# Connectivity.net
KiCad netlist of a schematic drawn in Altium Designer
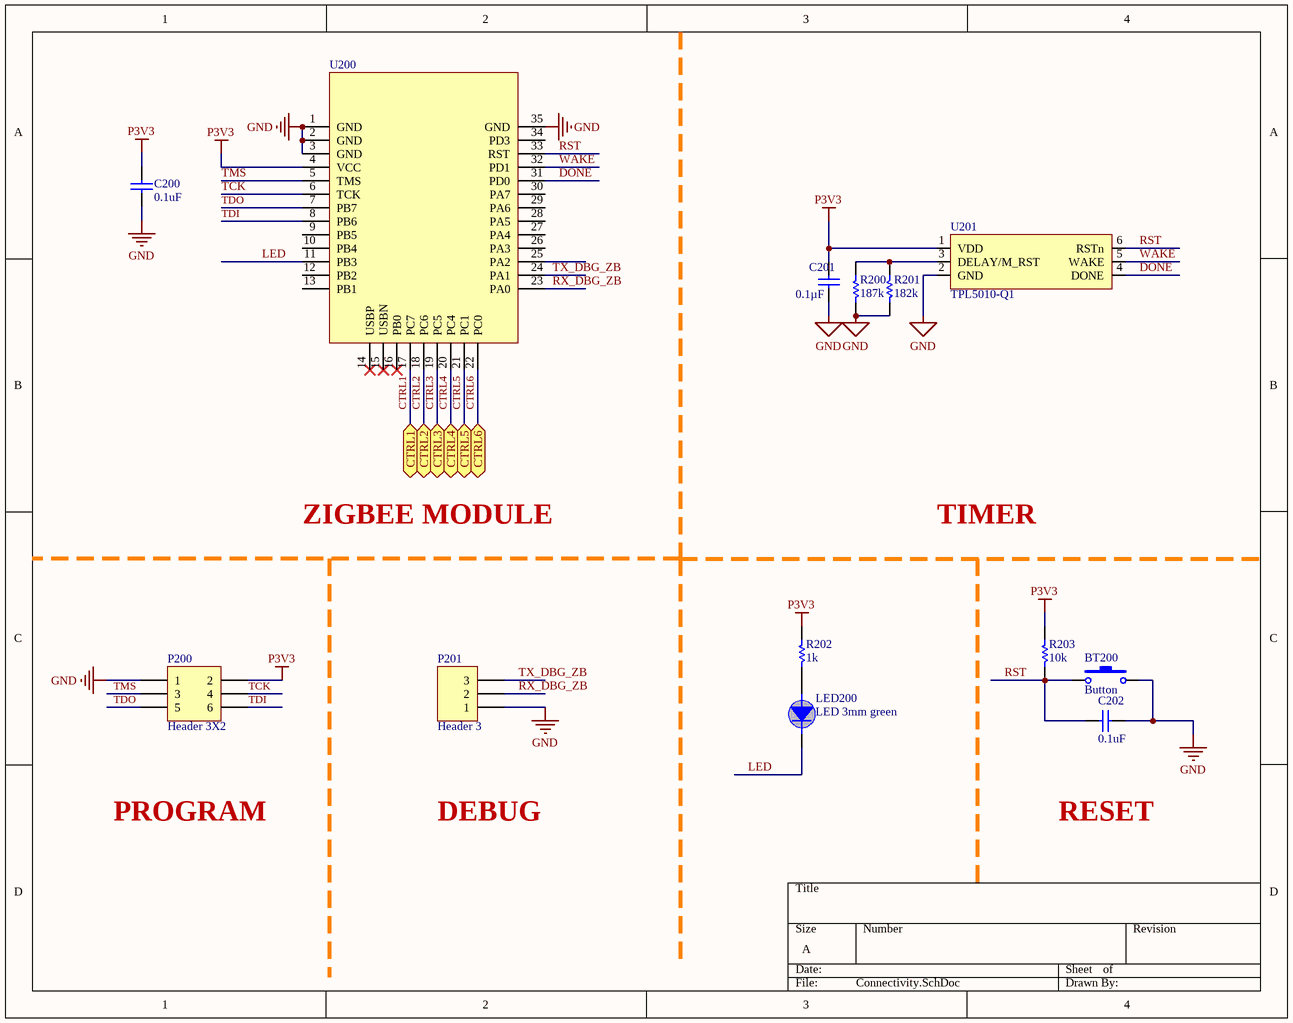
[diagram p0: Connectivity.SchDoc]

(export (version "E")
  (design (tool "Eeschema 10.0.6"))
  (components
    (comp (ref "BT200") (value "Button") (footprint "SWSMD") (libsource (lib "BinhLib") (part "Button")))
    (comp (ref "C200")
      (value "0.1uF")
      (footprint "0805 cap")
      (description "CAP CER 0.1UF 16V X7R 0402")
      (fields
        (field (name "MANUFACTURER") "Samsung Electro-Mechanics")
        (field (name "MANUFACTURER PART NUMBER") "CL05B104KO5NNNC")
      )
      (libsource (lib "BinhLib") (part "CAP0.1u0402"))
    )
    (comp (ref "C201")
      (value "0.1µF")
      (footprint "0805 cap")
      (description "CAP CER 0.1UF 10V X7R 0402")
      (fields
        (field (name "MANUFACTURER") "Taiyo Yuden")
        (field (name "MANUFACTURER PART NUMBER") "LMK105B7104KVHF")
      )
      (libsource (lib "BinhLib") (part "CAP0.1u0402"))
    )
    (comp (ref "C202") (value "0.1uF") (footprint "0805 cap") (libsource (lib "BinhLib") (part "cap SMD")))
    (comp (ref "LED200")
      (value "LED 3mm green")
      (footprint "LED 3mm green")
      (libsource (lib "BinhLib") (part "LED 3mm green"))
    )
    (comp (ref "P200")
      (value "Header 3X2")
      (footprint "HDR2X3")
      (description "Header, 3-Pin, Dual row")
      (fields (field (name "PUBLISHER") "Altium Limited"))
      (libsource (lib "BinhLib") (part "Header 3X2"))
    )
    (comp (ref "P201")
      (value "Header 3")
      (footprint "HDR1X3")
      (description "Header, 3-Pin")
      (fields (field (name "PUBLISHER") "Altium Limited"))
      (libsource (lib "BinhLib") (part "Header 3"))
    )
    (comp (ref "R200")
      (value "187k")
      (footprint "0805 Resistor")
      (description "RES SMD 187K OHM 1% 1/10W 0603")
      (fields
        (field (name "MANUFACTURER") "Panasonic Electronic Components")
        (field (name "MANUFACTURER PART NUMBER") "ERJ-3EKF1873V")
      )
      (libsource (lib "BinhLib") (part "Resistor"))
    )
    (comp (ref "R201")
      (value "182k")
      (footprint "0805 Resistor")
      (description "RES SMD 182K OHM 1% 1/10W 0603")
      (fields
        (field (name "MANUFACTURER") "Panasonic Electronic Components")
        (field (name "MANUFACTURER PART NUMBER") "ERJ-3EKF1823V")
      )
      (libsource (lib "BinhLib") (part "Resistor"))
    )
    (comp (ref "R202") (value "1k") (footprint "0805 Resistor") (libsource (lib "BinhLib") (part "Resistor")))
    (comp (ref "R203")
      (value "10k")
      (footprint "0805 Resistor")
      (libsource (lib "BinhLib") (part "Resistor"))
    )
    (comp (ref "U200")
      (value "~")
      (footprint "VZIGMOD2")
      (description "VNPT ZIGBEE MODULE V1 - No-PA")
      (fields
        (field (name "MANUFACTURER") "VNPT-Technology")
        (field (name "MANUFACTURER PART NUMBER") "VZIGMOD1")
      )
      (libsource (lib "SensorNode") (part "VZIGMOD2"))
    )
    (comp (ref "U201")
      (value "TPL5010-Q1")
      (footprint "SOT23-6")
      (description "IC TIMER W/WATCHDOG 6SOT")
      (fields
        (field (name "MANUFACTURER") "Texas Instruments")
        (field (name "MANUFACTURER PART NUMBER") "TPL5010QDDCRQ1")
      )
      (libsource (lib "BinhLib") (part "TPL5010"))
    )
  )
  (nets
    (net (code "1") (name "/CTRL1") (class "Default")
      (node (ref "U200") (pin "17") (pinfunction "PC7_17") (pintype "passive"))
    )
    (net (code "2") (name "/CTRL2") (class "Default")
      (node (ref "U200") (pin "18") (pinfunction "PC6_18") (pintype "passive"))
    )
    (net (code "3") (name "/CTRL3") (class "Default")
      (node (ref "U200") (pin "19") (pinfunction "PC5_19") (pintype "passive"))
    )
    (net (code "4") (name "/CTRL4") (class "Default")
      (node (ref "U200") (pin "20") (pinfunction "PC4_20") (pintype "passive"))
    )
    (net (code "5") (name "/CTRL5") (class "Default")
      (node (ref "U200") (pin "21") (pinfunction "PC1_21") (pintype "passive"))
    )
    (net (code "6") (name "/CTRL6") (class "Default")
      (node (ref "U200") (pin "22") (pinfunction "PC0_22") (pintype "passive"))
    )
    (net (code "7") (name "/DONE") (class "Default")
      (node (ref "U200") (pin "31") (pinfunction "PD0_31") (pintype "passive"))
      (node (ref "U201") (pin "4") (pinfunction "DONE_4") (pintype "passive"))
    )
    (net (code "8") (name "/LED") (class "Default")
      (node (ref "LED200") (pin "2") (pinfunction "Katot_2") (pintype "passive"))
      (node (ref "U200") (pin "11") (pinfunction "PB3_11") (pintype "passive"))
    )
    (net (code "9") (name "/RST") (class "Default")
      (node (ref "BT200") (pin "1") (pinfunction "1_1") (pintype "passive"))
      (node (ref "C202") (pin "2") (pintype "passive"))
      (node (ref "R203") (pin "1") (pinfunction "1_1") (pintype "passive"))
      (node (ref "U200") (pin "33") (pinfunction "RST_33") (pintype "passive"))
      (node (ref "U201") (pin "6") (pinfunction "RSTn_6") (pintype "passive"))
    )
    (net (code "10") (name "/RX_DBG_ZB") (class "Default")
      (node (ref "P201") (pin "2") (pinfunction "2_2") (pintype "passive"))
      (node (ref "U200") (pin "23") (pinfunction "PA0_23") (pintype "passive"))
    )
    (net (code "11") (name "/TCK") (class "Default")
      (node (ref "P200") (pin "4") (pinfunction "4_4") (pintype "passive"))
      (node (ref "U200") (pin "6") (pinfunction "TCK_6") (pintype "passive"))
    )
    (net (code "12") (name "/TDI") (class "Default")
      (node (ref "P200") (pin "6") (pinfunction "6_6") (pintype "passive"))
      (node (ref "U200") (pin "8") (pinfunction "PB6_8") (pintype "passive"))
    )
    (net (code "13") (name "/TDO") (class "Default")
      (node (ref "P200") (pin "5") (pinfunction "5_5") (pintype "passive"))
      (node (ref "U200") (pin "7") (pinfunction "PB7_7") (pintype "passive"))
    )
    (net (code "14") (name "/TMS") (class "Default")
      (node (ref "P200") (pin "3") (pinfunction "3_3") (pintype "passive"))
      (node (ref "U200") (pin "5") (pinfunction "TMS_5") (pintype "passive"))
    )
    (net (code "15") (name "/TX_DBG_ZB") (class "Default")
      (node (ref "P201") (pin "3") (pinfunction "3_3") (pintype "passive"))
      (node (ref "U200") (pin "24") (pinfunction "PA1_24") (pintype "passive"))
    )
    (net (code "16") (name "/WAKE") (class "Default")
      (node (ref "U200") (pin "32") (pinfunction "PD1_32") (pintype "passive"))
      (node (ref "U201") (pin "5") (pinfunction "WAKE_5") (pintype "passive"))
    )
    (net (code "17") (name "GND") (class "Default")
      (node (ref "BT200") (pin "2") (pinfunction "2_2") (pintype "passive"))
      (node (ref "C200") (pin "1") (pintype "passive"))
      (node (ref "C201") (pin "1") (pintype "passive"))
      (node (ref "C202") (pin "1") (pintype "passive"))
      (node (ref "P200") (pin "1") (pinfunction "1_1") (pintype "passive"))
      (node (ref "P201") (pin "1") (pinfunction "1_1") (pintype "passive"))
      (node (ref "R200") (pin "1") (pinfunction "1_1") (pintype "passive"))
      (node (ref "R201") (pin "1") (pinfunction "1_1") (pintype "passive"))
      (node (ref "U200") (pin "1") (pinfunction "GND_1") (pintype "passive"))
      (node (ref "U200") (pin "2") (pinfunction "GND_2") (pintype "passive"))
      (node (ref "U200") (pin "3") (pinfunction "GND_3") (pintype "passive"))
      (node (ref "U200") (pin "35") (pinfunction "GND_35") (pintype "passive"))
      (node (ref "U201") (pin "2") (pinfunction "GND_2") (pintype "passive"))
    )
    (net (code "18") (name "Net-(LED200-anot)") (class "Default")
      (node (ref "LED200") (pin "1") (pinfunction "anot_1") (pintype "passive"))
      (node (ref "R202") (pin "1") (pinfunction "1_1") (pintype "passive"))
    )
    (net (code "19") (name "Net-(U201-DELAY{slash}M_RST)") (class "Default")
      (node (ref "R200") (pin "2") (pinfunction "2_2") (pintype "passive"))
      (node (ref "R201") (pin "2") (pinfunction "2_2") (pintype "passive"))
      (node (ref "U201") (pin "3") (pinfunction "DELAY/M_RST_3") (pintype "passive"))
    )
    (net (code "20") (name "P3V3") (class "Default")
      (node (ref "C200") (pin "2") (pintype "passive"))
      (node (ref "C201") (pin "2") (pintype "passive"))
      (node (ref "P200") (pin "2") (pinfunction "2_2") (pintype "passive"))
      (node (ref "R202") (pin "2") (pinfunction "2_2") (pintype "passive"))
      (node (ref "R203") (pin "2") (pinfunction "2_2") (pintype "passive"))
      (node (ref "U200") (pin "4") (pinfunction "VCC_4") (pintype "passive"))
      (node (ref "U201") (pin "1") (pinfunction "VDD_1") (pintype "passive"))
    )
    (net (code "21") (name "unconnected-(U200-PA2-Pad25)") (class "Default")
      (node (ref "U200") (pin "25") (pinfunction "PA2_25") (pintype "passive"))
    )
    (net (code "22") (name "unconnected-(U200-PA3-Pad26)") (class "Default")
      (node (ref "U200") (pin "26") (pinfunction "PA3_26") (pintype "passive"))
    )
    (net (code "23") (name "unconnected-(U200-PA4-Pad27)") (class "Default")
      (node (ref "U200") (pin "27") (pinfunction "PA4_27") (pintype "passive"))
    )
    (net (code "24") (name "unconnected-(U200-PA5-Pad28)") (class "Default")
      (node (ref "U200") (pin "28") (pinfunction "PA5_28") (pintype "passive"))
    )
    (net (code "25") (name "unconnected-(U200-PA6-Pad29)") (class "Default")
      (node (ref "U200") (pin "29") (pinfunction "PA6_29") (pintype "passive"))
    )
    (net (code "26") (name "unconnected-(U200-PA7-Pad30)") (class "Default")
      (node (ref "U200") (pin "30") (pinfunction "PA7_30") (pintype "passive"))
    )
    (net (code "27") (name "unconnected-(U200-PB0-Pad16)") (class "Default")
      (node (ref "U200") (pin "16") (pinfunction "PB0_16") (pintype "passive+no_connect"))
    )
    (net (code "28") (name "unconnected-(U200-PB1-Pad13)") (class "Default")
      (node (ref "U200") (pin "13") (pinfunction "PB1_13") (pintype "passive"))
    )
    (net (code "29") (name "unconnected-(U200-PB2-Pad12)") (class "Default")
      (node (ref "U200") (pin "12") (pinfunction "PB2_12") (pintype "passive"))
    )
    (net (code "30") (name "unconnected-(U200-PB4-Pad10)") (class "Default")
      (node (ref "U200") (pin "10") (pinfunction "PB4_10") (pintype "passive"))
    )
    (net (code "31") (name "unconnected-(U200-PB5-Pad9)") (class "Default")
      (node (ref "U200") (pin "9") (pinfunction "PB5_9") (pintype "passive"))
    )
    (net (code "32") (name "unconnected-(U200-PD3-Pad34)") (class "Default")
      (node (ref "U200") (pin "34") (pinfunction "PD3_34") (pintype "passive"))
    )
    (net (code "33") (name "unconnected-(U200-USBN-Pad15)") (class "Default")
      (node (ref "U200") (pin "15") (pinfunction "USBN_15") (pintype "passive+no_connect"))
    )
    (net (code "34") (name "unconnected-(U200-USBP-Pad14)") (class "Default")
      (node (ref "U200") (pin "14") (pinfunction "USBP_14") (pintype "passive+no_connect"))
    )
  )
)
